# Wacky_Racers_extras.net
KiCad netlist of a schematic drawn in Altium Designer
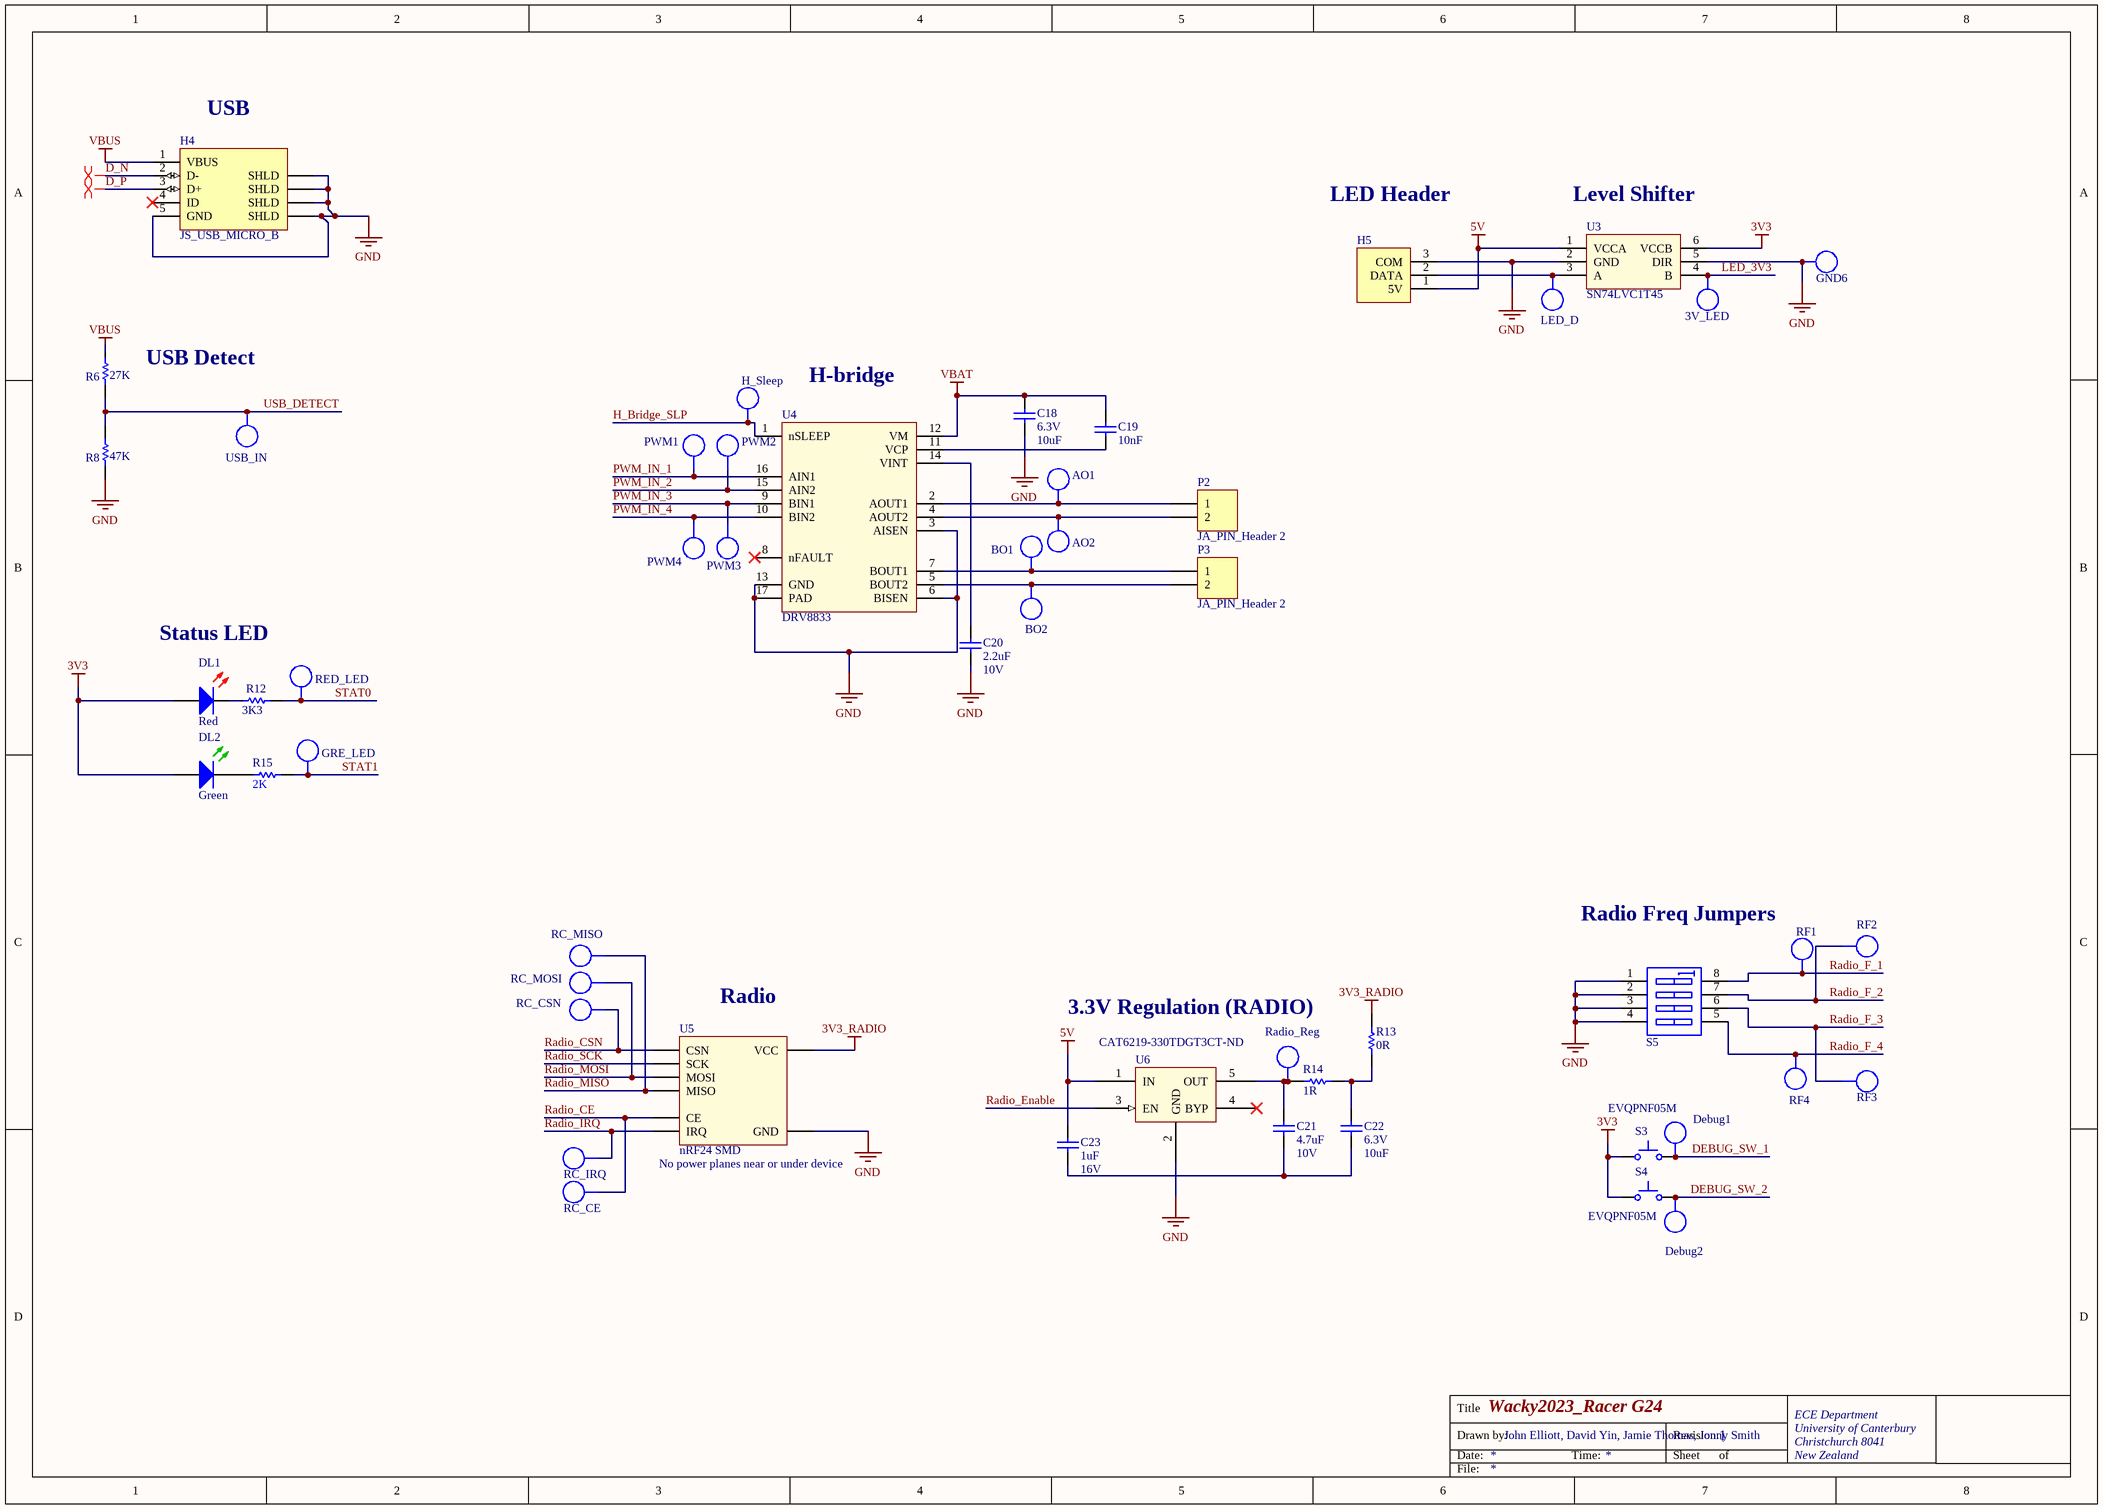
[diagram p0: Wacky_Racers_extras.SchDoc]

(export (version "E")
  (design (tool "Eeschema 10.0.6"))
  (components
    (comp (ref "3V_LED")
      (value "TP")
      (footprint "TP_1206")
      (description "Test-Point 3.3x1.6x2.1mm SMD")
      (fields
        (field (name "MANUFACTURER") "Harwin Inc")
        (field (name "MANUFACTURER PART NUMBER") "S1751-46R")
      )
      (libsource (lib "ECE AD19Components_22V1") (part "TP_1206"))
    )
    (comp (ref "AO1")
      (value "TP")
      (footprint "TP_1206")
      (description "Test-Point 3.3x1.6x2.1mm SMD")
      (fields
        (field (name "MANUFACTURER") "Harwin Inc")
        (field (name "MANUFACTURER PART NUMBER") "S1751-46R")
      )
      (libsource (lib "ECE AD19Components_22V1") (part "TP_1206"))
    )
    (comp (ref "AO2")
      (value "TP")
      (footprint "TP_1206")
      (description "Test-Point 3.3x1.6x2.1mm SMD")
      (fields
        (field (name "MANUFACTURER") "Harwin Inc")
        (field (name "MANUFACTURER PART NUMBER") "S1751-46R")
      )
      (libsource (lib "ECE AD19Components_22V1") (part "TP_1206"))
    )
    (comp (ref "BO1")
      (value "TP")
      (footprint "TP_1206")
      (description "Test-Point 3.3x1.6x2.1mm SMD")
      (fields
        (field (name "MANUFACTURER") "Harwin Inc")
        (field (name "MANUFACTURER PART NUMBER") "S1751-46R")
      )
      (libsource (lib "ECE AD19Components_22V1") (part "TP_1206"))
    )
    (comp (ref "BO2")
      (value "TP")
      (footprint "TP_1206")
      (description "Test-Point 3.3x1.6x2.1mm SMD")
      (fields
        (field (name "MANUFACTURER") "Harwin Inc")
        (field (name "MANUFACTURER PART NUMBER") "S1751-46R")
      )
      (libsource (lib "ECE AD19Components_22V1") (part "TP_1206"))
    )
    (comp (ref "C18")
      (value "10uF")
      (footprint "CAPC1608L")
      (description "CAP CER 10UF X5R +-20% 6V3 0603")
      (fields (field (name "VOLTAGE - RATED") "6.3V"))
      (libsource (lib "ECE AD19Components_22V1") (part "CC_10uF_0603"))
    )
    (comp (ref "C19")
      (value "10nF")
      (footprint "CAPC1608L")
      (description "CAP CER 10nF X7R +-10% 50V 0603")
      (libsource (lib "ECE AD19Components_22V1") (part "CC_10nF_0603"))
    )
    (comp (ref "C20")
      (value "2.2uF")
      (footprint "CAPC1608L")
      (description "CAP CER 2.2uF X5R +-20% 10V 0603")
      (fields (field (name "MAX VOLTAGE") "10V"))
      (libsource (lib "ECE AD19Components_22V1") (part "CC_2.2uF_0603"))
    )
    (comp (ref "C21")
      (value "4.7uF")
      (footprint "CAPC1608N")
      (description "CAP CER 4.7uF X5R +-20%  10V 0603")
      (fields (field (name "MAX VOLTAGE") "10V"))
      (libsource (lib "ECE AD19Components_22V1") (part "CC_4.7uF_0603"))
    )
    (comp (ref "C22")
      (value "10uF")
      (footprint "CAPC1608L")
      (description "CAP CER 10UF X5R +-20% 6V3 0603")
      (fields (field (name "VOLTAGE - RATED") "6.3V"))
      (libsource (lib "ECE AD19Components_22V1") (part "CC_10uF_0603"))
    )
    (comp (ref "C23")
      (value "1uF")
      (footprint "CAPC1608L")
      (description "CAP CER 1uF Y5V -20% +80% 16V 0603")
      (fields (field (name "MAX VOLTAGE") "16V"))
      (libsource (lib "ECE AD19Components_22V1") (part "CC_1uF_0603"))
    )
    (comp (ref "Debug1")
      (value "TP")
      (footprint "TP_1206")
      (description "Test-Point 3.3x1.6x2.1mm SMD")
      (fields
        (field (name "MANUFACTURER") "Harwin Inc")
        (field (name "MANUFACTURER PART NUMBER") "S1751-46R")
      )
      (libsource (lib "ECE AD19Components_22V1") (part "TP_1206"))
    )
    (comp (ref "Debug2")
      (value "TP")
      (footprint "TP_1206")
      (description "Test-Point 3.3x1.6x2.1mm SMD")
      (fields
        (field (name "MANUFACTURER") "Harwin Inc")
        (field (name "MANUFACTURER PART NUMBER") "S1751-46R")
      )
      (libsource (lib "ECE AD19Components_22V1") (part "TP_1206"))
    )
    (comp (ref "DL1")
      (value "Red")
      (footprint "WL-SMCW0603")
      (description "LED Red 250mcd 0603 SMD")
      (fields
        (field (name "MANUFACTURER") "WURTH ELEKTRONIK")
        (field (name "MANUFACTURER PART NUMBER") "150060RS75000")
        (field (name "LED COLOUR") "Red")
      )
      (libsource (lib "ECE AD19Components_22V1") (part "DL_150060RS75000"))
    )
    (comp (ref "DL2")
      (value "Green")
      (footprint "WL-SMCW0603")
      (description "LED Green 430mcd 0603 SMD")
      (fields
        (field (name "MANUFACTURER") "WURTH ELEKTRONIK")
        (field (name "MANUFACTURER PART NUMBER") "150060GS75000")
        (field (name "LED COLOUR") "Green")
      )
      (libsource (lib "ECE AD19Components_22V1") (part "DL_150060GS75000"))
    )
    (comp (ref "GND6")
      (value "TP")
      (footprint "TP_1206")
      (description "Test-Point 3.3x1.6x2.1mm SMD")
      (fields
        (field (name "MANUFACTURER") "Harwin Inc")
        (field (name "MANUFACTURER PART NUMBER") "S1751-46R")
      )
      (libsource (lib "ECE AD19Components_22V1") (part "TP_1206"))
    )
    (comp (ref "GRE_LED")
      (value "TP")
      (footprint "TP_1206")
      (description "Test-Point 3.3x1.6x2.1mm SMD")
      (fields
        (field (name "MANUFACTURER") "Harwin Inc")
        (field (name "MANUFACTURER PART NUMBER") "S1751-46R")
      )
      (libsource (lib "ECE AD19Components_22V1") (part "TP_1206"))
    )
    (comp (ref "H4")
      (value "JS_USB_MICRO_B")
      (footprint "FCI_USB_10118194-0001LF")
      (description "CONN USB MICRO B RECPT SMT R/A")
      (fields (field (name "MANUFACTURER") "FCI") (field (name "MANUFACTURER PART NUMBER") "10118194-0001LF"))
      (libsource (lib "ECE AD19Components_22V1") (part "JS_USB_MICRO_B_SMT"))
    )
    (comp (ref "H5")
      (value "3 Pin Molex KK Hdr")
      (footprint "MOLEX_KK_3_HDR")
      (description "CONN HEADER 3POS 2.54mm VERT_Thru Hole")
      (fields (field (name "MANUFACTURER") "Molex"))
      (libsource (lib "ENCE461AD19_V23") (part "LED_Strip_Header"))
    )
    (comp (ref "H_Sleep")
      (value "TP")
      (footprint "TP_1206")
      (description "Test-Point 3.3x1.6x2.1mm SMD")
      (fields
        (field (name "MANUFACTURER") "Harwin Inc")
        (field (name "MANUFACTURER PART NUMBER") "S1751-46R")
      )
      (libsource (lib "ECE AD19Components_22V1") (part "TP_1206"))
    )
    (comp (ref "LED_D")
      (value "TP")
      (footprint "TP_1206")
      (description "Test-Point 3.3x1.6x2.1mm SMD")
      (fields
        (field (name "MANUFACTURER") "Harwin Inc")
        (field (name "MANUFACTURER PART NUMBER") "S1751-46R")
      )
      (libsource (lib "ECE AD19Components_22V1") (part "TP_1206"))
    )
    (comp (ref "P2")
      (value "JA_PIN_Header 2")
      (footprint "HDR1X2")
      (description "Header, 2-Pin")
      (fields (field (name "PUBLISHER") "Altium Limited"))
      (libsource (lib "ECE AD19Components_22V1") (part "JA_PIN_Header 2"))
    )
    (comp (ref "P3")
      (value "JA_PIN_Header 2")
      (footprint "HDR1X2")
      (description "Header, 2-Pin")
      (fields (field (name "PUBLISHER") "Altium Limited"))
      (libsource (lib "ECE AD19Components_22V1") (part "JA_PIN_Header 2"))
    )
    (comp (ref "PWM1")
      (value "TP")
      (footprint "TP_1206")
      (description "Test-Point 3.3x1.6x2.1mm SMD")
      (fields
        (field (name "MANUFACTURER") "Harwin Inc")
        (field (name "MANUFACTURER PART NUMBER") "S1751-46R")
      )
      (libsource (lib "ECE AD19Components_22V1") (part "TP_1206"))
    )
    (comp (ref "PWM2")
      (value "TP")
      (footprint "TP_1206")
      (description "Test-Point 3.3x1.6x2.1mm SMD")
      (fields
        (field (name "MANUFACTURER") "Harwin Inc")
        (field (name "MANUFACTURER PART NUMBER") "S1751-46R")
      )
      (libsource (lib "ECE AD19Components_22V1") (part "TP_1206"))
    )
    (comp (ref "PWM3")
      (value "TP")
      (footprint "TP_1206")
      (description "Test-Point 3.3x1.6x2.1mm SMD")
      (fields
        (field (name "MANUFACTURER") "Harwin Inc")
        (field (name "MANUFACTURER PART NUMBER") "S1751-46R")
      )
      (libsource (lib "ECE AD19Components_22V1") (part "TP_1206"))
    )
    (comp (ref "PWM4")
      (value "TP")
      (footprint "TP_1206")
      (description "Test-Point 3.3x1.6x2.1mm SMD")
      (fields
        (field (name "MANUFACTURER") "Harwin Inc")
        (field (name "MANUFACTURER PART NUMBER") "S1751-46R")
      )
      (libsource (lib "ECE AD19Components_22V1") (part "TP_1206"))
    )
    (comp (ref "R6")
      (value "27K")
      (footprint "RESC1608L")
      (description "RES 27K OHM 1/10W 5% 0603 SMD")
      (libsource (lib "ECE AD19Components_22V1") (part "RS_27K"))
    )
    (comp (ref "R8")
      (value "47K")
      (footprint "RESC1608N")
      (description "RES 47.0K OHM 1/10W 5% 0603 SMD")
      (libsource (lib "ECE AD19Components_22V1") (part "RS_47K"))
    )
    (comp (ref "R12")
      (value "3K3")
      (footprint "RESC1608L")
      (description "RES 3.3K OHM 1/10W 5% 0603 SMD")
      (libsource (lib "ECE AD19Components_22V1") (part "RS_3K3"))
    )
    (comp (ref "R13")
      (value "0R")
      (footprint "RESC1608L")
      (description "RES 0.0 OHM 1/10W 5% 0603 SMD")
      (libsource (lib "ECE AD19Components_22V1") (part "RS_0R0"))
    )
    (comp (ref "R14")
      (value "1R")
      (footprint "RESC3216L")
      (description "RES 1R OHM 1/4W 5% 1206 SMD")
      (libsource (lib "ECE AD19Components_22V1") (part "RT_1R"))
    )
    (comp (ref "R15")
      (value "2K")
      (footprint "RESC1608L")
      (description "RES 2K OHM 1/10W 5% 0603 SMD")
      (libsource (lib "ECE AD19Components_22V1") (part "RS_2K"))
    )
    (comp (ref "Radio_Reg")
      (value "TP")
      (footprint "TP_1206")
      (description "Test-Point 3.3x1.6x2.1mm SMD")
      (fields
        (field (name "MANUFACTURER") "Harwin Inc")
        (field (name "MANUFACTURER PART NUMBER") "S1751-46R")
      )
      (libsource (lib "ECE AD19Components_22V1") (part "TP_1206"))
    )
    (comp (ref "RC_CE")
      (value "TP")
      (footprint "TP_1206")
      (description "Test-Point 3.3x1.6x2.1mm SMD")
      (fields
        (field (name "MANUFACTURER") "Harwin Inc")
        (field (name "MANUFACTURER PART NUMBER") "S1751-46R")
      )
      (libsource (lib "ECE AD19Components_22V1") (part "TP_1206"))
    )
    (comp (ref "RC_CSN")
      (value "TP")
      (footprint "TP_1206")
      (description "Test-Point 3.3x1.6x2.1mm SMD")
      (fields
        (field (name "MANUFACTURER") "Harwin Inc")
        (field (name "MANUFACTURER PART NUMBER") "S1751-46R")
      )
      (libsource (lib "ECE AD19Components_22V1") (part "TP_1206"))
    )
    (comp (ref "RC_IRQ")
      (value "TP")
      (footprint "TP_1206")
      (description "Test-Point 3.3x1.6x2.1mm SMD")
      (fields
        (field (name "MANUFACTURER") "Harwin Inc")
        (field (name "MANUFACTURER PART NUMBER") "S1751-46R")
      )
      (libsource (lib "ECE AD19Components_22V1") (part "TP_1206"))
    )
    (comp (ref "RC_MISO")
      (value "TP")
      (footprint "TP_1206")
      (description "Test-Point 3.3x1.6x2.1mm SMD")
      (fields
        (field (name "MANUFACTURER") "Harwin Inc")
        (field (name "MANUFACTURER PART NUMBER") "S1751-46R")
      )
      (libsource (lib "ECE AD19Components_22V1") (part "TP_1206"))
    )
    (comp (ref "RC_MOSI")
      (value "TP")
      (footprint "TP_1206")
      (description "Test-Point 3.3x1.6x2.1mm SMD")
      (fields
        (field (name "MANUFACTURER") "Harwin Inc")
        (field (name "MANUFACTURER PART NUMBER") "S1751-46R")
      )
      (libsource (lib "ECE AD19Components_22V1") (part "TP_1206"))
    )
    (comp (ref "RED_LED")
      (value "TP")
      (footprint "TP_1206")
      (description "Test-Point 3.3x1.6x2.1mm SMD")
      (fields
        (field (name "MANUFACTURER") "Harwin Inc")
        (field (name "MANUFACTURER PART NUMBER") "S1751-46R")
      )
      (libsource (lib "ECE AD19Components_22V1") (part "TP_1206"))
    )
    (comp (ref "RF1")
      (value "TP")
      (footprint "TP_1206")
      (description "Test-Point 3.3x1.6x2.1mm SMD")
      (fields
        (field (name "MANUFACTURER") "Harwin Inc")
        (field (name "MANUFACTURER PART NUMBER") "S1751-46R")
      )
      (libsource (lib "ECE AD19Components_22V1") (part "TP_1206"))
    )
    (comp (ref "RF2")
      (value "TP")
      (footprint "TP_1206")
      (description "Test-Point 3.3x1.6x2.1mm SMD")
      (fields
        (field (name "MANUFACTURER") "Harwin Inc")
        (field (name "MANUFACTURER PART NUMBER") "S1751-46R")
      )
      (libsource (lib "ECE AD19Components_22V1") (part "TP_1206"))
    )
    (comp (ref "RF3")
      (value "TP")
      (footprint "TP_1206")
      (description "Test-Point 3.3x1.6x2.1mm SMD")
      (fields
        (field (name "MANUFACTURER") "Harwin Inc")
        (field (name "MANUFACTURER PART NUMBER") "S1751-46R")
      )
      (libsource (lib "ECE AD19Components_22V1") (part "TP_1206"))
    )
    (comp (ref "RF4")
      (value "TP")
      (footprint "TP_1206")
      (description "Test-Point 3.3x1.6x2.1mm SMD")
      (fields
        (field (name "MANUFACTURER") "Harwin Inc")
        (field (name "MANUFACTURER PART NUMBER") "S1751-46R")
      )
      (libsource (lib "ECE AD19Components_22V1") (part "TP_1206"))
    )
    (comp (ref "S3")
      (value "EVQPNF05M")
      (footprint "EVQPNF05M")
      (description "Panasonic 6 x 3.5mm SMD Light Touch Switch Type SMD")
      (fields (field (name "MANUFACTURER") "Panasonic"))
      (libsource (lib "ECE AD19Components_22V1") (part "WS_EVQPNF05M"))
    )
    (comp (ref "S4")
      (value "EVQPNF05M")
      (footprint "EVQPNF05M")
      (description "Panasonic 6 x 3.5mm SMD Light Touch Switch Type SMD")
      (fields (field (name "MANUFACTURER") "Panasonic"))
      (libsource (lib "ECE AD19Components_22V1") (part "WS_EVQPNF05M"))
    )
    (comp (ref "S5")
      (value "WS_SW DIP-4")
      (footprint "DIP_SW_4WAY_SMD -")
      (description "DIP Switch, 4 Position, SPST SMD")
      (fields
        (field (name "MANUFACTURER") "OMRON ELECTRONIC COMPONENTS")
        (field (name "MANUFACTURER PART NUMBER") "A6SN-4101")
      )
      (libsource (lib "ECE AD19Components_22V1") (part "WS_SW DIP-4"))
    )
    (comp (ref "U3")
      (value "SN74LVC1T45")
      (footprint "SOT23-6_N")
      (description "1.8V - 5V level converter")
      (libsource (lib "ENCE461AD19_V23") (part "SN74LVC1T45"))
    )
    (comp (ref "U4")
      (value "DRV8833")
      (footprint "HTSOP16 DRV8833")
      (description "Dual H-Bridge Motor Driver 1.5A")
      (libsource (lib "ENCE461AD19_V23") (part "DRV8833"))
    )
    (comp (ref "U5")
      (value "nRF24 SMD")
      (footprint "NRF24")
      (description "nRF24 SMD Module")
      (fields (field (name "WARNING") "No power planes near or under device"))
      (libsource (lib "ENCE461AD19_V23") (part "NRF24"))
    )
    (comp (ref "U6")
      (value "CAT6219-330TDGT3")
      (footprint "SOT95P280X145-5N")
      (description "IC REG LIN 3.3V 500MA TSOT23-5")
      (fields
        (field (name "BASE PART NUMBER") "CAT6219")
        (field (name "SUPPLIER PART NUMBER") "CAT6219-330TDGT3CT-ND")
      )
      (libsource (lib "ENCE461AD19_V23") (part "SV_CAT6219-330TDGT3"))
    )
    (comp (ref "USB_IN")
      (value "TP")
      (footprint "TP_1206")
      (description "Test-Point 3.3x1.6x2.1mm SMD")
      (fields
        (field (name "MANUFACTURER") "Harwin Inc")
        (field (name "MANUFACTURER PART NUMBER") "S1751-46R")
      )
      (libsource (lib "ECE AD19Components_22V1") (part "TP_1206"))
    )
  )
  (nets
    (net (code "1") (name "/DEBUG_SW_1") (class "Default")
      (node (ref "Debug1") (pin "1") (pinfunction "1_1") (pintype "passive"))
      (node (ref "S3") (pin "2") (pintype "passive"))
    )
    (net (code "2") (name "/DEBUG_SW_2") (class "Default")
      (node (ref "Debug2") (pin "1") (pinfunction "1_1") (pintype "passive"))
      (node (ref "S4") (pin "2") (pintype "passive"))
    )
    (net (code "3") (name "/D_N") (class "Default")
      (node (ref "H4") (pin "2") (pinfunction "D-_2") (pintype "bidirectional"))
    )
    (net (code "4") (name "/D_P") (class "Default")
      (node (ref "H4") (pin "3") (pinfunction "D+_3") (pintype "bidirectional"))
    )
    (net (code "5") (name "/H_Bridge_SLP") (class "Default")
      (node (ref "H_Sleep") (pin "1") (pinfunction "1_1") (pintype "passive"))
      (node (ref "U4") (pin "1") (pinfunction "nSLEEP_1") (pintype "passive"))
    )
    (net (code "6") (name "/LED_3V3") (class "Default")
      (node (ref "3V_LED") (pin "1") (pinfunction "1_1") (pintype "passive"))
      (node (ref "U3") (pin "4") (pinfunction "B_4") (pintype "passive"))
    )
    (net (code "7") (name "/PWM_IN_1") (class "Default")
      (node (ref "PWM1") (pin "1") (pinfunction "1_1") (pintype "passive"))
      (node (ref "U4") (pin "16") (pinfunction "AIN1_16") (pintype "passive"))
    )
    (net (code "8") (name "/PWM_IN_2") (class "Default")
      (node (ref "PWM2") (pin "1") (pinfunction "1_1") (pintype "passive"))
      (node (ref "U4") (pin "15") (pinfunction "AIN2_15") (pintype "passive"))
    )
    (net (code "9") (name "/PWM_IN_3") (class "Default")
      (node (ref "PWM3") (pin "1") (pinfunction "1_1") (pintype "passive"))
      (node (ref "U4") (pin "9") (pinfunction "BIN1_9") (pintype "passive"))
    )
    (net (code "10") (name "/PWM_IN_4") (class "Default")
      (node (ref "PWM4") (pin "1") (pinfunction "1_1") (pintype "passive"))
      (node (ref "U4") (pin "10") (pinfunction "BIN2_10") (pintype "passive"))
    )
    (net (code "11") (name "/Radio_CE") (class "Default")
      (node (ref "RC_CE") (pin "1") (pinfunction "1_1") (pintype "passive"))
      (node (ref "U5") (pin "3") (pinfunction "CE_3") (pintype "passive"))
    )
    (net (code "12") (name "/Radio_CSN") (class "Default")
      (node (ref "RC_CSN") (pin "1") (pinfunction "1_1") (pintype "passive"))
      (node (ref "U5") (pin "4") (pinfunction "CSN_4") (pintype "passive"))
    )
    (net (code "13") (name "/Radio_Enable") (class "Default")
      (node (ref "U6") (pin "3") (pinfunction "EN_3") (pintype "input"))
    )
    (net (code "14") (name "/Radio_F_1") (class "Default")
      (node (ref "RF1") (pin "1") (pinfunction "1_1") (pintype "passive"))
      (node (ref "S5") (pin "8") (pinfunction "B1_8") (pintype "passive"))
    )
    (net (code "15") (name "/Radio_F_2") (class "Default")
      (node (ref "RF2") (pin "1") (pinfunction "1_1") (pintype "passive"))
      (node (ref "S5") (pin "7") (pinfunction "B2_7") (pintype "passive"))
    )
    (net (code "16") (name "/Radio_F_3") (class "Default")
      (node (ref "RF3") (pin "1") (pinfunction "1_1") (pintype "passive"))
      (node (ref "S5") (pin "6") (pinfunction "B3_6") (pintype "passive"))
    )
    (net (code "17") (name "/Radio_F_4") (class "Default")
      (node (ref "RF4") (pin "1") (pinfunction "1_1") (pintype "passive"))
      (node (ref "S5") (pin "5") (pinfunction "B4_5") (pintype "passive"))
    )
    (net (code "18") (name "/Radio_IRQ") (class "Default")
      (node (ref "RC_IRQ") (pin "1") (pinfunction "1_1") (pintype "passive"))
      (node (ref "U5") (pin "8") (pinfunction "IRQ_8") (pintype "passive"))
    )
    (net (code "19") (name "/Radio_MISO") (class "Default")
      (node (ref "RC_MISO") (pin "1") (pinfunction "1_1") (pintype "passive"))
      (node (ref "U5") (pin "7") (pinfunction "MISO_7") (pintype "passive"))
    )
    (net (code "20") (name "/Radio_MOSI") (class "Default")
      (node (ref "RC_MOSI") (pin "1") (pinfunction "1_1") (pintype "passive"))
      (node (ref "U5") (pin "6") (pinfunction "MOSI_6") (pintype "passive"))
    )
    (net (code "21") (name "/Radio_SCK") (class "Default")
      (node (ref "U5") (pin "5") (pinfunction "SCK_5") (pintype "passive"))
    )
    (net (code "22") (name "/STAT0") (class "Default")
      (node (ref "R12") (pin "2") (pinfunction "2_2") (pintype "passive"))
      (node (ref "RED_LED") (pin "1") (pinfunction "1_1") (pintype "passive"))
    )
    (net (code "23") (name "/STAT1") (class "Default")
      (node (ref "GRE_LED") (pin "1") (pinfunction "1_1") (pintype "passive"))
      (node (ref "R15") (pin "2") (pinfunction "2_2") (pintype "passive"))
    )
    (net (code "24") (name "/USB_DETECT") (class "Default")
      (node (ref "R6") (pin "1") (pinfunction "1_1") (pintype "passive"))
      (node (ref "R8") (pin "2") (pinfunction "2_2") (pintype "passive"))
      (node (ref "USB_IN") (pin "1") (pinfunction "1_1") (pintype "passive"))
    )
    (net (code "25") (name "3V3") (class "Default")
      (node (ref "DL1") (pin "2") (pinfunction "A_2") (pintype "passive"))
      (node (ref "DL2") (pin "2") (pinfunction "A_2") (pintype "passive"))
      (node (ref "S3") (pin "1") (pintype "passive"))
      (node (ref "S4") (pin "1") (pintype "passive"))
      (node (ref "U3") (pin "6") (pinfunction "VCCB_6") (pintype "passive"))
    )
    (net (code "26") (name "3V3_RADIO") (class "Default")
      (node (ref "R13") (pin "2") (pinfunction "2_2") (pintype "passive"))
      (node (ref "U5") (pin "1") (pinfunction "VCC_1") (pintype "passive"))
    )
    (net (code "27") (name "5V") (class "Default")
      (node (ref "C23") (pin "2") (pinfunction "2_2") (pintype "passive"))
      (node (ref "H5") (pin "1") (pinfunction "5V_1") (pintype "passive"))
      (node (ref "U3") (pin "1") (pinfunction "VCCA_1") (pintype "passive"))
      (node (ref "U6") (pin "1") (pinfunction "IN_1") (pintype "power_in"))
    )
    (net (code "28") (name "GND") (class "Default")
      (node (ref "C18") (pin "1") (pinfunction "1_1") (pintype "passive"))
      (node (ref "C20") (pin "1") (pinfunction "1_1") (pintype "passive"))
      (node (ref "GND6") (pin "1") (pinfunction "1_1") (pintype "passive"))
      (node (ref "H4") (pin "5") (pinfunction "GND_5") (pintype "passive"))
      (node (ref "H4") (pin "6") (pinfunction "SHLD_6") (pintype "passive"))
      (node (ref "H5") (pin "3") (pinfunction "COM_3") (pintype "passive"))
      (node (ref "R8") (pin "1") (pinfunction "1_1") (pintype "passive"))
      (node (ref "S5") (pin "1") (pinfunction "A1_1") (pintype "passive"))
      (node (ref "S5") (pin "2") (pinfunction "A2_2") (pintype "passive"))
      (node (ref "S5") (pin "3") (pinfunction "A3_3") (pintype "passive"))
      (node (ref "S5") (pin "4") (pinfunction "A4_4") (pintype "passive"))
      (node (ref "U3") (pin "2") (pinfunction "GND_2") (pintype "passive"))
      (node (ref "U3") (pin "5") (pinfunction "DIR_5") (pintype "passive"))
      (node (ref "U4") (pin "13") (pinfunction "GND_13") (pintype "passive"))
      (node (ref "U4") (pin "17") (pinfunction "PAD_17") (pintype "passive"))
      (node (ref "U4") (pin "3") (pinfunction "AISEN_3") (pintype "passive"))
      (node (ref "U4") (pin "6") (pinfunction "BISEN_6") (pintype "passive"))
      (node (ref "U5") (pin "2") (pinfunction "GND_2") (pintype "passive"))
      (node (ref "U6") (pin "2") (pinfunction "GND_2") (pintype "power_in"))
    )
    (net (code "29") (name "Net-(C21-Pad1)") (class "Default")
      (node (ref "C21") (pin "1") (pinfunction "1_1") (pintype "passive"))
      (node (ref "C22") (pin "1") (pinfunction "1_1") (pintype "passive"))
      (node (ref "C23") (pin "1") (pinfunction "1_1") (pintype "passive"))
    )
    (net (code "30") (name "Net-(C22-Pad2)") (class "Default")
      (node (ref "C22") (pin "2") (pinfunction "2_2") (pintype "passive"))
      (node (ref "R13") (pin "1") (pinfunction "1_1") (pintype "passive"))
      (node (ref "R14") (pin "2") (pinfunction "2_2") (pintype "passive"))
    )
    (net (code "31") (name "Net-(DL1-K)") (class "Default")
      (node (ref "DL1") (pin "1") (pinfunction "K_1") (pintype "passive"))
      (node (ref "R12") (pin "1") (pinfunction "1_1") (pintype "passive"))
    )
    (net (code "32") (name "Net-(DL2-K)") (class "Default")
      (node (ref "DL2") (pin "1") (pinfunction "K_1") (pintype "passive"))
      (node (ref "R15") (pin "1") (pinfunction "1_1") (pintype "passive"))
    )
    (net (code "33") (name "Net-(H5-DATA)") (class "Default")
      (node (ref "H5") (pin "2") (pinfunction "DATA_2") (pintype "passive"))
      (node (ref "LED_D") (pin "1") (pinfunction "1_1") (pintype "passive"))
      (node (ref "U3") (pin "3") (pinfunction "A_3") (pintype "passive"))
    )
    (net (code "34") (name "Net-(U4-AOUT1)") (class "Default")
      (node (ref "AO1") (pin "1") (pinfunction "1_1") (pintype "passive"))
      (node (ref "P2") (pin "1") (pinfunction "1_1") (pintype "passive"))
      (node (ref "U4") (pin "2") (pinfunction "AOUT1_2") (pintype "passive"))
    )
    (net (code "35") (name "Net-(U4-AOUT2)") (class "Default")
      (node (ref "AO2") (pin "1") (pinfunction "1_1") (pintype "passive"))
      (node (ref "P2") (pin "2") (pinfunction "2_2") (pintype "passive"))
      (node (ref "U4") (pin "4") (pinfunction "AOUT2_4") (pintype "passive"))
    )
    (net (code "36") (name "Net-(U4-BOUT1)") (class "Default")
      (node (ref "BO1") (pin "1") (pinfunction "1_1") (pintype "passive"))
      (node (ref "P3") (pin "1") (pinfunction "1_1") (pintype "passive"))
      (node (ref "U4") (pin "7") (pinfunction "BOUT1_7") (pintype "passive"))
    )
    (net (code "37") (name "Net-(U4-BOUT2)") (class "Default")
      (node (ref "BO2") (pin "1") (pinfunction "1_1") (pintype "passive"))
      (node (ref "P3") (pin "2") (pinfunction "2_2") (pintype "passive"))
      (node (ref "U4") (pin "5") (pinfunction "BOUT2_5") (pintype "passive"))
    )
    (net (code "38") (name "Net-(U4-VCP)") (class "Default")
      (node (ref "C19") (pin "1") (pinfunction "1_1") (pintype "passive"))
      (node (ref "U4") (pin "11") (pinfunction "VCP_11") (pintype "passive"))
    )
    (net (code "39") (name "Net-(U4-VINT)") (class "Default")
      (node (ref "C20") (pin "2") (pinfunction "2_2") (pintype "passive"))
      (node (ref "U4") (pin "14") (pinfunction "VINT_14") (pintype "passive"))
    )
    (net (code "40") (name "Net-(U6-OUT)") (class "Default")
      (node (ref "C21") (pin "2") (pinfunction "2_2") (pintype "passive"))
      (node (ref "R14") (pin "1") (pinfunction "1_1") (pintype "passive"))
      (node (ref "Radio_Reg") (pin "1") (pinfunction "1_1") (pintype "passive"))
      (node (ref "U6") (pin "5") (pinfunction "OUT_5") (pintype "power_in"))
    )
    (net (code "41") (name "VBAT") (class "Default")
      (node (ref "C18") (pin "2") (pinfunction "2_2") (pintype "passive"))
      (node (ref "C19") (pin "2") (pinfunction "2_2") (pintype "passive"))
      (node (ref "U4") (pin "12") (pinfunction "VM_12") (pintype "passive"))
    )
    (net (code "42") (name "VBUS") (class "Default")
      (node (ref "H4") (pin "1") (pinfunction "VBUS_1") (pintype "power_in"))
      (node (ref "R6") (pin "2") (pinfunction "2_2") (pintype "passive"))
    )
    (net (code "43") (name "unconnected-(H4-ID-Pad4)") (class "Default")
      (node (ref "H4") (pin "4") (pinfunction "ID_4") (pintype "power_in+no_connect"))
    )
    (net (code "44") (name "unconnected-(U4-nFAULT-Pad8)") (class "Default")
      (node (ref "U4") (pin "8") (pinfunction "nFAULT_8") (pintype "passive+no_connect"))
    )
    (net (code "45") (name "unconnected-(U6-BYP-Pad4)") (class "Default")
      (node (ref "U6") (pin "4") (pinfunction "BYP_4") (pintype "passive+no_connect"))
    )
  )
)
